# Cool-S-Budget.net
KiCad netlist of a schematic drawn in EAGLE
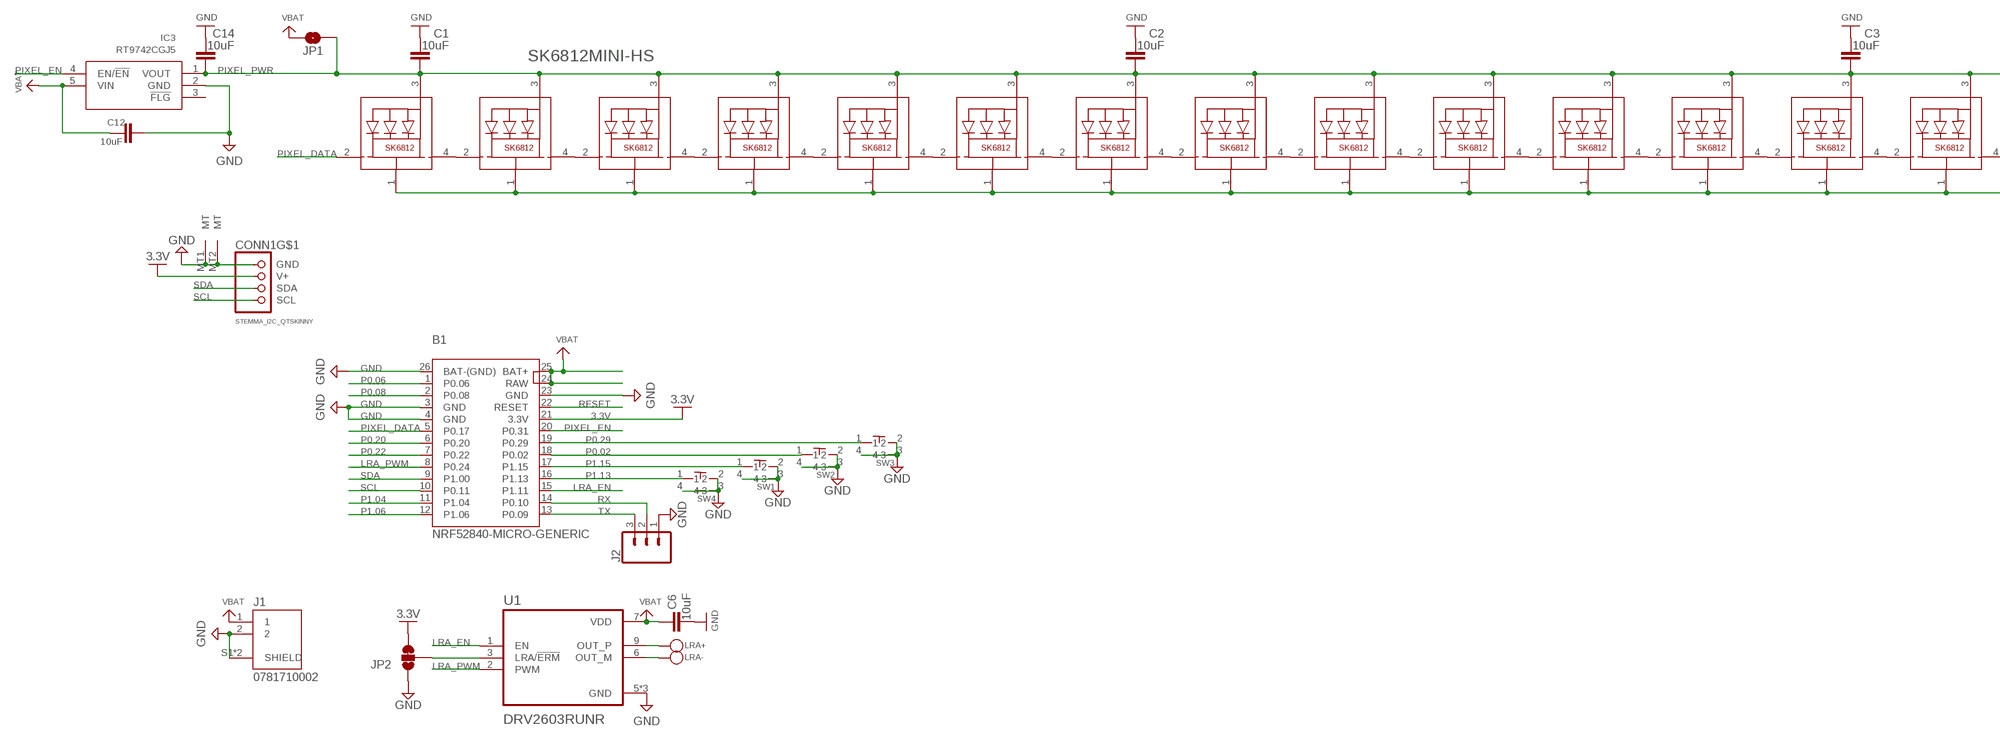
[diagram p0: schematic, sheet 1, part 1 of 2]
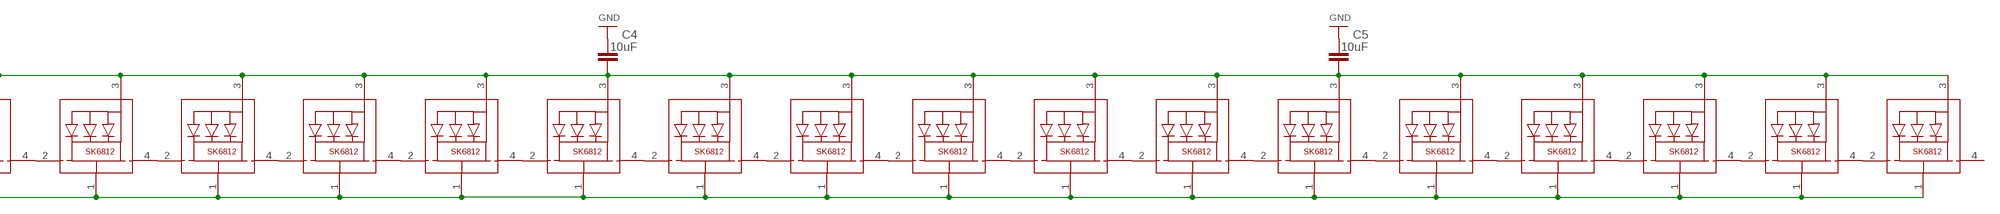
[diagram p1: schematic, sheet 1, part 2 of 2]

(export (version "E")
  (design (tool "Eeschema 10.0.6"))
  (components
    (comp (ref "B1")
      (value "NRF52840-MICRO-GENERIC")
      (footprint "eagle-import:NRF52840-MICRO-GENERIC")
      (libsource (lib "eagle-import") (part "NRF52840-MICRO-GENERIC"))
    )
    (comp (ref "C1")
      (value "10uF")
      (footprint "eagle-import:CAPC1608X85")
      (libsource (lib "eagle-import") (part "CCHIP-0603(1608-METRIC)_"))
    )
    (comp (ref "C2")
      (value "10uF")
      (footprint "eagle-import:CAPC1608X85")
      (libsource (lib "eagle-import") (part "CCHIP-0603(1608-METRIC)_"))
    )
    (comp (ref "C3")
      (value "10uF")
      (footprint "eagle-import:CAPC1608X85")
      (libsource (lib "eagle-import") (part "CCHIP-0603(1608-METRIC)_"))
    )
    (comp (ref "C4")
      (value "10uF")
      (footprint "eagle-import:CAPC1608X85")
      (libsource (lib "eagle-import") (part "CCHIP-0603(1608-METRIC)_"))
    )
    (comp (ref "C5")
      (value "10uF")
      (footprint "eagle-import:CAPC1608X85")
      (libsource (lib "eagle-import") (part "CCHIP-0603(1608-METRIC)_"))
    )
    (comp (ref "C6")
      (value "10uF")
      (footprint "eagle-import:CAPC1608X85")
      (libsource (lib "eagle-import") (part "CCHIP-0603(1608-METRIC)_"))
    )
    (comp (ref "C12")
      (value "10uF")
      (footprint "eagle-import:CAPC1608X85")
      (libsource (lib "eagle-import") (part "CCHIP-0603(1608-METRIC)_"))
    )
    (comp (ref "C14")
      (value "10uF")
      (footprint "eagle-import:CAPC1608X85")
      (libsource (lib "eagle-import") (part "CCHIP-0603(1608-METRIC)_"))
    )
    (comp (ref "CONN1")
      (value "STEMMA_I2C_QTSKINNY")
      (footprint "eagle-import:JST_SH4_SKINNY")
      (libsource (lib "eagle-import") (part "STEMMA_I2C_QTSKINNY"))
    )
    (comp (ref "IC3")
      (value "RT9742CGJ5")
      (footprint "eagle-import:SOT94P280X100-5N")
      (fields
        (field (name "MANUFACTURER_PART_NUMBER") "RT9742GGJ5")
        (field (name "MOUSER_PART_NUMBER") "835-RT9742GGJ5")
      )
      (libsource (lib "eagle-import") (part "RT9742GGJ5"))
    )
    (comp (ref "J1")
      (value "0781710002")
      (footprint "eagle-import:MOLEX_0781710002")
      (fields (field (name "MANUFACTURER") "MOLEX"))
      (libsource (lib "eagle-import") (part "0781710002"))
    )
    (comp (ref "J2")
      (value "455-1750-1-ND")
      (footprint "eagle-import:1X03")
      (libsource (lib "eagle-import") (part "CONN_03"))
    )
    (comp (ref "JP1")
      (value "JUMPER-SMT_2_NO_NO-SILK")
      (footprint "eagle-import:SMT-JUMPER_2_NO_NO-SILK")
      (libsource (lib "eagle-import") (part "JUMPER-SMT_2_NO_NO-SILK"))
    )
    (comp (ref "JP2")
      (value "JUMPER-SMT_3_1-NC_TRACE_NO-SILK")
      (footprint "eagle-import:SMT-JUMPER_3_1-NC_TRACE_NO-SILK")
      (libsource (lib "eagle-import") (part "JUMPER-SMT_3_1-NC_TRACE_NO-SILK"))
    )
    (comp (ref "LRA+")
      (value "TESTPOINT")
      (footprint "eagle-import:TESTPOINT_SMT")
      (libsource (lib "eagle-import") (part "TESTPOINT"))
    )
    (comp (ref "LRA-")
      (value "TESTPOINT")
      (footprint "eagle-import:TESTPOINT_SMT")
      (libsource (lib "eagle-import") (part "TESTPOINT"))
    )
    (comp (ref "SW1")
      (value "TS36CA-0.6250GF031SW-SMD_SHOU_TS36CA-0.6")
      (footprint "eagle-import:SW-SMD_SHOU_TS36CA-0.6")
      (libsource (lib "eagle-import") (part "TS36CA-0.6250GF031SW-SMD_SHOU_TS36CA-0.6"))
    )
    (comp (ref "SW2")
      (value "TS36CA-0.6250GF031SW-SMD_SHOU_TS36CA-0.6")
      (footprint "eagle-import:SW-SMD_SHOU_TS36CA-0.6")
      (libsource (lib "eagle-import") (part "TS36CA-0.6250GF031SW-SMD_SHOU_TS36CA-0.6"))
    )
    (comp (ref "SW3")
      (value "TS36CA-0.6250GF031SW-SMD_SHOU_TS36CA-0.6")
      (footprint "eagle-import:SW-SMD_SHOU_TS36CA-0.6")
      (libsource (lib "eagle-import") (part "TS36CA-0.6250GF031SW-SMD_SHOU_TS36CA-0.6"))
    )
    (comp (ref "SW4")
      (value "TS36CA-0.6250GF031SW-SMD_SHOU_TS36CA-0.6")
      (footprint "eagle-import:SW-SMD_SHOU_TS36CA-0.6")
      (libsource (lib "eagle-import") (part "TS36CA-0.6250GF031SW-SMD_SHOU_TS36CA-0.6"))
    )
    (comp (ref "U1")
      (value "DRV2603RUNR")
      (footprint "eagle-import:QFN50P200X200X80-10N")
      (fields (field (name "MF") "Texas Instruments"))
      (libsource (lib "eagle-import") (part "DRV2603RUNR"))
    )
    (comp (ref "U3")
      (value "SK6812MINI")
      (footprint "eagle-import:LED3535")
      (libsource (lib "eagle-import") (part "SK6812MINI"))
    )
    (comp (ref "U4")
      (value "SK6812MINI")
      (footprint "eagle-import:LED3535")
      (libsource (lib "eagle-import") (part "SK6812MINI"))
    )
    (comp (ref "U5")
      (value "SK6812MINI")
      (footprint "eagle-import:LED3535")
      (libsource (lib "eagle-import") (part "SK6812MINI"))
    )
    (comp (ref "U6")
      (value "SK6812MINI")
      (footprint "eagle-import:LED3535")
      (libsource (lib "eagle-import") (part "SK6812MINI"))
    )
    (comp (ref "U7")
      (value "SK6812MINI")
      (footprint "eagle-import:LED3535")
      (libsource (lib "eagle-import") (part "SK6812MINI"))
    )
    (comp (ref "U8")
      (value "SK6812MINI")
      (footprint "eagle-import:LED3535")
      (libsource (lib "eagle-import") (part "SK6812MINI"))
    )
    (comp (ref "U9")
      (value "SK6812MINI")
      (footprint "eagle-import:LED3535")
      (libsource (lib "eagle-import") (part "SK6812MINI"))
    )
    (comp (ref "U10")
      (value "SK6812MINI")
      (footprint "eagle-import:LED3535")
      (libsource (lib "eagle-import") (part "SK6812MINI"))
    )
    (comp (ref "U11")
      (value "SK6812MINI")
      (footprint "eagle-import:LED3535")
      (libsource (lib "eagle-import") (part "SK6812MINI"))
    )
    (comp (ref "U12")
      (value "SK6812MINI")
      (footprint "eagle-import:LED3535")
      (libsource (lib "eagle-import") (part "SK6812MINI"))
    )
    (comp (ref "U13")
      (value "SK6812MINI")
      (footprint "eagle-import:LED3535")
      (libsource (lib "eagle-import") (part "SK6812MINI"))
    )
    (comp (ref "U14")
      (value "SK6812MINI")
      (footprint "eagle-import:LED3535")
      (libsource (lib "eagle-import") (part "SK6812MINI"))
    )
    (comp (ref "U15")
      (value "SK6812MINI")
      (footprint "eagle-import:LED3535")
      (libsource (lib "eagle-import") (part "SK6812MINI"))
    )
    (comp (ref "U16")
      (value "SK6812MINI")
      (footprint "eagle-import:LED3535")
      (libsource (lib "eagle-import") (part "SK6812MINI"))
    )
    (comp (ref "U17")
      (value "SK6812MINI")
      (footprint "eagle-import:LED3535")
      (libsource (lib "eagle-import") (part "SK6812MINI"))
    )
    (comp (ref "U18")
      (value "SK6812MINI")
      (footprint "eagle-import:LED3535")
      (libsource (lib "eagle-import") (part "SK6812MINI"))
    )
    (comp (ref "U19")
      (value "SK6812MINI")
      (footprint "eagle-import:LED3535")
      (libsource (lib "eagle-import") (part "SK6812MINI"))
    )
    (comp (ref "U20")
      (value "SK6812MINI")
      (footprint "eagle-import:LED3535")
      (libsource (lib "eagle-import") (part "SK6812MINI"))
    )
    (comp (ref "U21")
      (value "SK6812MINI")
      (footprint "eagle-import:LED3535")
      (libsource (lib "eagle-import") (part "SK6812MINI"))
    )
    (comp (ref "U22")
      (value "SK6812MINI")
      (footprint "eagle-import:LED3535")
      (libsource (lib "eagle-import") (part "SK6812MINI"))
    )
    (comp (ref "U23")
      (value "SK6812MINI")
      (footprint "eagle-import:LED3535")
      (libsource (lib "eagle-import") (part "SK6812MINI"))
    )
    (comp (ref "U24")
      (value "SK6812MINI")
      (footprint "eagle-import:LED3535")
      (libsource (lib "eagle-import") (part "SK6812MINI"))
    )
    (comp (ref "U25")
      (value "SK6812MINI")
      (footprint "eagle-import:LED3535")
      (libsource (lib "eagle-import") (part "SK6812MINI"))
    )
    (comp (ref "U26")
      (value "SK6812MINI")
      (footprint "eagle-import:LED3535")
      (libsource (lib "eagle-import") (part "SK6812MINI"))
    )
    (comp (ref "U27")
      (value "SK6812MINI")
      (footprint "eagle-import:LED3535")
      (libsource (lib "eagle-import") (part "SK6812MINI"))
    )
    (comp (ref "U28")
      (value "SK6812MINI")
      (footprint "eagle-import:LED3535")
      (libsource (lib "eagle-import") (part "SK6812MINI"))
    )
    (comp (ref "U29")
      (value "SK6812MINI")
      (footprint "eagle-import:LED3535")
      (libsource (lib "eagle-import") (part "SK6812MINI"))
    )
    (comp (ref "U30")
      (value "SK6812MINI")
      (footprint "eagle-import:LED3535")
      (libsource (lib "eagle-import") (part "SK6812MINI"))
    )
    (comp (ref "U31")
      (value "SK6812MINI")
      (footprint "eagle-import:LED3535")
      (libsource (lib "eagle-import") (part "SK6812MINI"))
    )
    (comp (ref "U32")
      (value "SK6812MINI")
      (footprint "eagle-import:LED3535")
      (libsource (lib "eagle-import") (part "SK6812MINI"))
    )
  )
  (nets
    (net (code "1") (name "/LRA_EN") (class "Default")
      (node (ref "B1") (pin "15") (pinfunction "P1.11_15") (pintype "bidirectional"))
      (node (ref "U1") (pin "1") (pinfunction "EN_1") (pintype "input"))
    )
    (net (code "2") (name "/LRA_PWM") (class "Default")
      (node (ref "B1") (pin "8") (pinfunction "P0.24_8") (pintype "bidirectional"))
      (node (ref "U1") (pin "2") (pinfunction "PWM_2") (pintype "input"))
    )
    (net (code "3") (name "/P0.02") (class "Default")
      (node (ref "B1") (pin "18") (pinfunction "P0.02_18") (pintype "bidirectional"))
      (node (ref "SW2") (pin "1") (pinfunction "1_1") (pintype "bidirectional"))
    )
    (net (code "4") (name "/P0.06") (class "Default")
      (node (ref "B1") (pin "1") (pinfunction "P0.06_1") (pintype "bidirectional"))
    )
    (net (code "5") (name "/P0.08") (class "Default")
      (node (ref "B1") (pin "2") (pinfunction "P0.08_2") (pintype "bidirectional"))
    )
    (net (code "6") (name "/P0.20") (class "Default")
      (node (ref "B1") (pin "6") (pinfunction "P0.20_6") (pintype "bidirectional"))
    )
    (net (code "7") (name "/P0.22") (class "Default")
      (node (ref "B1") (pin "7") (pinfunction "P0.22_7") (pintype "bidirectional"))
    )
    (net (code "8") (name "/P0.29") (class "Default")
      (node (ref "B1") (pin "19") (pinfunction "P0.29_19") (pintype "bidirectional"))
      (node (ref "SW3") (pin "1") (pinfunction "1_1") (pintype "bidirectional"))
    )
    (net (code "9") (name "/P1.04") (class "Default")
      (node (ref "B1") (pin "11") (pinfunction "P1.04_11") (pintype "bidirectional"))
    )
    (net (code "10") (name "/P1.06") (class "Default")
      (node (ref "B1") (pin "12") (pinfunction "P1.06_12") (pintype "bidirectional"))
    )
    (net (code "11") (name "/P1.13") (class "Default")
      (node (ref "B1") (pin "16") (pinfunction "P1.13_16") (pintype "bidirectional"))
      (node (ref "SW4") (pin "1") (pinfunction "1_1") (pintype "bidirectional"))
    )
    (net (code "12") (name "/P1.15") (class "Default")
      (node (ref "B1") (pin "17") (pinfunction "P1.15_17") (pintype "bidirectional"))
      (node (ref "SW1") (pin "1") (pinfunction "1_1") (pintype "bidirectional"))
    )
    (net (code "13") (name "/PIXEL_DATA") (class "Default")
      (node (ref "B1") (pin "5") (pinfunction "P0.17_5") (pintype "bidirectional"))
      (node (ref "U32") (pin "2") (pinfunction "DI_2") (pintype "input"))
    )
    (net (code "14") (name "/PIXEL_EN") (class "Default")
      (node (ref "B1") (pin "20") (pinfunction "P0.31_20") (pintype "bidirectional"))
      (node (ref "IC3") (pin "4") (pinfunction "EN/~{EN}_4") (pintype "bidirectional"))
    )
    (net (code "15") (name "/PIXEL_PWR") (class "Default")
      (node (ref "C1") (pin "2") (pinfunction "2_2") (pintype "passive"))
      (node (ref "C14") (pin "2") (pinfunction "2_2") (pintype "passive"))
      (node (ref "C2") (pin "2") (pinfunction "2_2") (pintype "passive"))
      (node (ref "C3") (pin "2") (pinfunction "2_2") (pintype "passive"))
      (node (ref "C4") (pin "2") (pinfunction "2_2") (pintype "passive"))
      (node (ref "C5") (pin "2") (pinfunction "2_2") (pintype "passive"))
      (node (ref "IC3") (pin "1") (pinfunction "VOUT_1") (pintype "bidirectional"))
      (node (ref "JP1") (pin "1") (pinfunction "1_1") (pintype "passive"))
      (node (ref "U10") (pin "3") (pinfunction "VDD_3") (pintype "power_in"))
      (node (ref "U11") (pin "3") (pinfunction "VDD_3") (pintype "power_in"))
      (node (ref "U12") (pin "3") (pinfunction "VDD_3") (pintype "power_in"))
      (node (ref "U13") (pin "3") (pinfunction "VDD_3") (pintype "power_in"))
      (node (ref "U14") (pin "3") (pinfunction "VDD_3") (pintype "power_in"))
      (node (ref "U15") (pin "3") (pinfunction "VDD_3") (pintype "power_in"))
      (node (ref "U16") (pin "3") (pinfunction "VDD_3") (pintype "power_in"))
      (node (ref "U17") (pin "3") (pinfunction "VDD_3") (pintype "power_in"))
      (node (ref "U18") (pin "3") (pinfunction "VDD_3") (pintype "power_in"))
      (node (ref "U19") (pin "3") (pinfunction "VDD_3") (pintype "power_in"))
      (node (ref "U20") (pin "3") (pinfunction "VDD_3") (pintype "power_in"))
      (node (ref "U21") (pin "3") (pinfunction "VDD_3") (pintype "power_in"))
      (node (ref "U22") (pin "3") (pinfunction "VDD_3") (pintype "power_in"))
      (node (ref "U23") (pin "3") (pinfunction "VDD_3") (pintype "power_in"))
      (node (ref "U24") (pin "3") (pinfunction "VDD_3") (pintype "power_in"))
      (node (ref "U25") (pin "3") (pinfunction "VDD_3") (pintype "power_in"))
      (node (ref "U26") (pin "3") (pinfunction "VDD_3") (pintype "power_in"))
      (node (ref "U27") (pin "3") (pinfunction "VDD_3") (pintype "power_in"))
      (node (ref "U28") (pin "3") (pinfunction "VDD_3") (pintype "power_in"))
      (node (ref "U29") (pin "3") (pinfunction "VDD_3") (pintype "power_in"))
      (node (ref "U3") (pin "3") (pinfunction "VDD_3") (pintype "power_in"))
      (node (ref "U30") (pin "3") (pinfunction "VDD_3") (pintype "power_in"))
      (node (ref "U31") (pin "3") (pinfunction "VDD_3") (pintype "power_in"))
      (node (ref "U32") (pin "3") (pinfunction "VDD_3") (pintype "power_in"))
      (node (ref "U4") (pin "3") (pinfunction "VDD_3") (pintype "power_in"))
      (node (ref "U5") (pin "3") (pinfunction "VDD_3") (pintype "power_in"))
      (node (ref "U6") (pin "3") (pinfunction "VDD_3") (pintype "power_in"))
      (node (ref "U7") (pin "3") (pinfunction "VDD_3") (pintype "power_in"))
      (node (ref "U8") (pin "3") (pinfunction "VDD_3") (pintype "power_in"))
      (node (ref "U9") (pin "3") (pinfunction "VDD_3") (pintype "power_in"))
    )
    (net (code "16") (name "/RESET") (class "Default")
      (node (ref "B1") (pin "22") (pinfunction "RESET_22") (pintype "bidirectional"))
    )
    (net (code "17") (name "/RX") (class "Default")
      (node (ref "B1") (pin "14") (pinfunction "P0.10_14") (pintype "bidirectional"))
      (node (ref "J2") (pin "2") (pinfunction "2_2") (pintype "passive"))
    )
    (net (code "18") (name "/SCL") (class "Default")
      (node (ref "B1") (pin "10") (pinfunction "P0.11_10") (pintype "bidirectional"))
      (node (ref "CONN1") (pin "4") (pinfunction "SCL_4") (pintype "passive"))
    )
    (net (code "19") (name "/SDA") (class "Default")
      (node (ref "B1") (pin "9") (pinfunction "P1.00_9") (pintype "bidirectional"))
      (node (ref "CONN1") (pin "3") (pinfunction "SDA_3") (pintype "passive"))
    )
    (net (code "20") (name "/TX") (class "Default")
      (node (ref "B1") (pin "13") (pinfunction "P0.09_13") (pintype "bidirectional"))
      (node (ref "J2") (pin "3") (pinfunction "3_3") (pintype "passive"))
    )
    (net (code "21") (name "3.3V") (class "Default")
      (node (ref "B1") (pin "21") (pinfunction "3.3V_21") (pintype "power_in"))
      (node (ref "CONN1") (pin "2") (pinfunction "V+_2") (pintype "passive"))
      (node (ref "JP2") (pin "3") (pinfunction "3_3") (pintype "passive"))
    )
    (net (code "22") (name "GND") (class "Default")
      (node (ref "B1") (pin "23") (pinfunction "GND_23") (pintype "power_in"))
      (node (ref "B1") (pin "26") (pinfunction "BAT-(GND)_26") (pintype "bidirectional"))
      (node (ref "B1") (pin "3") (pinfunction "GND_3") (pintype "power_in"))
      (node (ref "B1") (pin "4") (pinfunction "GND_4") (pintype "power_in"))
      (node (ref "C1") (pin "1") (pinfunction "1_1") (pintype "passive"))
      (node (ref "C12") (pin "2") (pinfunction "2_2") (pintype "passive"))
      (node (ref "C14") (pin "1") (pinfunction "1_1") (pintype "passive"))
      (node (ref "C2") (pin "1") (pinfunction "1_1") (pintype "passive"))
      (node (ref "C3") (pin "1") (pinfunction "1_1") (pintype "passive"))
      (node (ref "C4") (pin "1") (pinfunction "1_1") (pintype "passive"))
      (node (ref "C5") (pin "1") (pinfunction "1_1") (pintype "passive"))
      (node (ref "C6") (pin "1") (pinfunction "1_1") (pintype "passive"))
      (node (ref "CONN1") (pin "1") (pinfunction "GND_1") (pintype "passive"))
      (node (ref "CONN1") (pin "MT1") (pinfunction "MT_MT1") (pintype "bidirectional"))
      (node (ref "CONN1") (pin "MT2") (pinfunction "MT_MT2") (pintype "bidirectional"))
      (node (ref "IC3") (pin "2") (pinfunction "GND_2") (pintype "bidirectional"))
      (node (ref "J1") (pin "2") (pinfunction "2_2") (pintype "passive"))
      (node (ref "J1") (pin "S1") (pinfunction "SHIELD_S1") (pintype "passive"))
      (node (ref "J1") (pin "S2") (pinfunction "SHIELD_S2") (pintype "passive"))
      (node (ref "J2") (pin "1") (pinfunction "1_1") (pintype "passive"))
      (node (ref "JP2") (pin "1") (pinfunction "1_1") (pintype "passive"))
      (node (ref "SW1") (pin "2") (pinfunction "2_2") (pintype "bidirectional"))
      (node (ref "SW1") (pin "3") (pinfunction "3_3") (pintype "bidirectional"))
      (node (ref "SW1") (pin "4") (pinfunction "4_4") (pintype "bidirectional"))
      (node (ref "SW2") (pin "2") (pinfunction "2_2") (pintype "bidirectional"))
      (node (ref "SW2") (pin "3") (pinfunction "3_3") (pintype "bidirectional"))
      (node (ref "SW2") (pin "4") (pinfunction "4_4") (pintype "bidirectional"))
      (node (ref "SW3") (pin "2") (pinfunction "2_2") (pintype "bidirectional"))
      (node (ref "SW3") (pin "3") (pinfunction "3_3") (pintype "bidirectional"))
      (node (ref "SW3") (pin "4") (pinfunction "4_4") (pintype "bidirectional"))
      (node (ref "SW4") (pin "2") (pinfunction "2_2") (pintype "bidirectional"))
      (node (ref "SW4") (pin "3") (pinfunction "3_3") (pintype "bidirectional"))
      (node (ref "SW4") (pin "4") (pinfunction "4_4") (pintype "bidirectional"))
      (node (ref "U1") (pin "10") (pinfunction "GND_10") (pintype "power_in"))
      (node (ref "U1") (pin "5") (pinfunction "GND_5") (pintype "power_in"))
      (node (ref "U1") (pin "8") (pinfunction "GND_8") (pintype "power_in"))
      (node (ref "U10") (pin "1") (pinfunction "GND_1") (pintype "power_in"))
      (node (ref "U11") (pin "1") (pinfunction "GND_1") (pintype "power_in"))
      (node (ref "U12") (pin "1") (pinfunction "GND_1") (pintype "power_in"))
      (node (ref "U13") (pin "1") (pinfunction "GND_1") (pintype "power_in"))
      (node (ref "U14") (pin "1") (pinfunction "GND_1") (pintype "power_in"))
      (node (ref "U15") (pin "1") (pinfunction "GND_1") (pintype "power_in"))
      (node (ref "U16") (pin "1") (pinfunction "GND_1") (pintype "power_in"))
      (node (ref "U17") (pin "1") (pinfunction "GND_1") (pintype "power_in"))
      (node (ref "U18") (pin "1") (pinfunction "GND_1") (pintype "power_in"))
      (node (ref "U19") (pin "1") (pinfunction "GND_1") (pintype "power_in"))
      (node (ref "U20") (pin "1") (pinfunction "GND_1") (pintype "power_in"))
      (node (ref "U21") (pin "1") (pinfunction "GND_1") (pintype "power_in"))
      (node (ref "U22") (pin "1") (pinfunction "GND_1") (pintype "power_in"))
      (node (ref "U23") (pin "1") (pinfunction "GND_1") (pintype "power_in"))
      (node (ref "U24") (pin "1") (pinfunction "GND_1") (pintype "power_in"))
      (node (ref "U25") (pin "1") (pinfunction "GND_1") (pintype "power_in"))
      (node (ref "U26") (pin "1") (pinfunction "GND_1") (pintype "power_in"))
      (node (ref "U27") (pin "1") (pinfunction "GND_1") (pintype "power_in"))
      (node (ref "U28") (pin "1") (pinfunction "GND_1") (pintype "power_in"))
      (node (ref "U29") (pin "1") (pinfunction "GND_1") (pintype "power_in"))
      (node (ref "U3") (pin "1") (pinfunction "GND_1") (pintype "power_in"))
      (node (ref "U30") (pin "1") (pinfunction "GND_1") (pintype "power_in"))
      (node (ref "U31") (pin "1") (pinfunction "GND_1") (pintype "power_in"))
      (node (ref "U32") (pin "1") (pinfunction "GND_1") (pintype "power_in"))
      (node (ref "U4") (pin "1") (pinfunction "GND_1") (pintype "power_in"))
      (node (ref "U5") (pin "1") (pinfunction "GND_1") (pintype "power_in"))
      (node (ref "U6") (pin "1") (pinfunction "GND_1") (pintype "power_in"))
      (node (ref "U7") (pin "1") (pinfunction "GND_1") (pintype "power_in"))
      (node (ref "U8") (pin "1") (pinfunction "GND_1") (pintype "power_in"))
      (node (ref "U9") (pin "1") (pinfunction "GND_1") (pintype "power_in"))
    )
    (net (code "23") (name "Net-(U1-LRA{slash}~{ERM})") (class "Default")
      (node (ref "JP2") (pin "2") (pinfunction "2_2") (pintype "passive"))
      (node (ref "U1") (pin "3") (pinfunction "LRA/~{ERM}_3") (pintype "input"))
    )
    (net (code "24") (name "Net-(U1-OUT_M)") (class "Default")
      (node (ref "LRA-") (pin "P$1") (pinfunction "P$1_P$1") (pintype "bidirectional"))
      (node (ref "U1") (pin "6") (pinfunction "OUT_M_6") (pintype "output"))
    )
    (net (code "25") (name "Net-(U1-OUT_P)") (class "Default")
      (node (ref "LRA+") (pin "P$1") (pinfunction "P$1_P$1") (pintype "bidirectional"))
      (node (ref "U1") (pin "9") (pinfunction "OUT_P_9") (pintype "output"))
    )
    (net (code "26") (name "Net-(U3-DI)") (class "Default")
      (node (ref "U3") (pin "2") (pinfunction "DI_2") (pintype "input"))
      (node (ref "U4") (pin "4") (pinfunction "DO_4") (pintype "output"))
    )
    (net (code "27") (name "Net-(U4-DI)") (class "Default")
      (node (ref "U4") (pin "2") (pinfunction "DI_2") (pintype "input"))
      (node (ref "U5") (pin "4") (pinfunction "DO_4") (pintype "output"))
    )
    (net (code "28") (name "Net-(U5-DI)") (class "Default")
      (node (ref "U5") (pin "2") (pinfunction "DI_2") (pintype "input"))
      (node (ref "U6") (pin "4") (pinfunction "DO_4") (pintype "output"))
    )
    (net (code "29") (name "Net-(U6-DI)") (class "Default")
      (node (ref "U6") (pin "2") (pinfunction "DI_2") (pintype "input"))
      (node (ref "U7") (pin "4") (pinfunction "DO_4") (pintype "output"))
    )
    (net (code "30") (name "Net-(U7-DI)") (class "Default")
      (node (ref "U7") (pin "2") (pinfunction "DI_2") (pintype "input"))
      (node (ref "U8") (pin "4") (pinfunction "DO_4") (pintype "output"))
    )
    (net (code "31") (name "Net-(U8-DI)") (class "Default")
      (node (ref "U8") (pin "2") (pinfunction "DI_2") (pintype "input"))
      (node (ref "U9") (pin "4") (pinfunction "DO_4") (pintype "output"))
    )
    (net (code "32") (name "Net-(U10-DI)") (class "Default")
      (node (ref "U10") (pin "2") (pinfunction "DI_2") (pintype "input"))
      (node (ref "U11") (pin "4") (pinfunction "DO_4") (pintype "output"))
    )
    (net (code "33") (name "Net-(U10-DO)") (class "Default")
      (node (ref "U10") (pin "4") (pinfunction "DO_4") (pintype "output"))
      (node (ref "U9") (pin "2") (pinfunction "DI_2") (pintype "input"))
    )
    (net (code "34") (name "Net-(U11-DI)") (class "Default")
      (node (ref "U11") (pin "2") (pinfunction "DI_2") (pintype "input"))
      (node (ref "U12") (pin "4") (pinfunction "DO_4") (pintype "output"))
    )
    (net (code "35") (name "Net-(U12-DI)") (class "Default")
      (node (ref "U12") (pin "2") (pinfunction "DI_2") (pintype "input"))
      (node (ref "U13") (pin "4") (pinfunction "DO_4") (pintype "output"))
    )
    (net (code "36") (name "Net-(U13-DI)") (class "Default")
      (node (ref "U13") (pin "2") (pinfunction "DI_2") (pintype "input"))
      (node (ref "U14") (pin "4") (pinfunction "DO_4") (pintype "output"))
    )
    (net (code "37") (name "Net-(U14-DI)") (class "Default")
      (node (ref "U14") (pin "2") (pinfunction "DI_2") (pintype "input"))
      (node (ref "U15") (pin "4") (pinfunction "DO_4") (pintype "output"))
    )
    (net (code "38") (name "Net-(U15-DI)") (class "Default")
      (node (ref "U15") (pin "2") (pinfunction "DI_2") (pintype "input"))
      (node (ref "U16") (pin "4") (pinfunction "DO_4") (pintype "output"))
    )
    (net (code "39") (name "Net-(U16-DI)") (class "Default")
      (node (ref "U16") (pin "2") (pinfunction "DI_2") (pintype "input"))
      (node (ref "U17") (pin "4") (pinfunction "DO_4") (pintype "output"))
    )
    (net (code "40") (name "Net-(U17-DI)") (class "Default")
      (node (ref "U17") (pin "2") (pinfunction "DI_2") (pintype "input"))
      (node (ref "U18") (pin "4") (pinfunction "DO_4") (pintype "output"))
    )
    (net (code "41") (name "Net-(U18-DI)") (class "Default")
      (node (ref "U18") (pin "2") (pinfunction "DI_2") (pintype "input"))
      (node (ref "U19") (pin "4") (pinfunction "DO_4") (pintype "output"))
    )
    (net (code "42") (name "Net-(U19-DI)") (class "Default")
      (node (ref "U19") (pin "2") (pinfunction "DI_2") (pintype "input"))
      (node (ref "U20") (pin "4") (pinfunction "DO_4") (pintype "output"))
    )
    (net (code "43") (name "Net-(U20-DI)") (class "Default")
      (node (ref "U20") (pin "2") (pinfunction "DI_2") (pintype "input"))
      (node (ref "U21") (pin "4") (pinfunction "DO_4") (pintype "output"))
    )
    (net (code "44") (name "Net-(U21-DI)") (class "Default")
      (node (ref "U21") (pin "2") (pinfunction "DI_2") (pintype "input"))
      (node (ref "U22") (pin "4") (pinfunction "DO_4") (pintype "output"))
    )
    (net (code "45") (name "Net-(U22-DI)") (class "Default")
      (node (ref "U22") (pin "2") (pinfunction "DI_2") (pintype "input"))
      (node (ref "U23") (pin "4") (pinfunction "DO_4") (pintype "output"))
    )
    (net (code "46") (name "Net-(U23-DI)") (class "Default")
      (node (ref "U23") (pin "2") (pinfunction "DI_2") (pintype "input"))
      (node (ref "U24") (pin "4") (pinfunction "DO_4") (pintype "output"))
    )
    (net (code "47") (name "Net-(U24-DI)") (class "Default")
      (node (ref "U24") (pin "2") (pinfunction "DI_2") (pintype "input"))
      (node (ref "U25") (pin "4") (pinfunction "DO_4") (pintype "output"))
    )
    (net (code "48") (name "Net-(U25-DI)") (class "Default")
      (node (ref "U25") (pin "2") (pinfunction "DI_2") (pintype "input"))
      (node (ref "U26") (pin "4") (pinfunction "DO_4") (pintype "output"))
    )
    (net (code "49") (name "Net-(U26-DI)") (class "Default")
      (node (ref "U26") (pin "2") (pinfunction "DI_2") (pintype "input"))
      (node (ref "U27") (pin "4") (pinfunction "DO_4") (pintype "output"))
    )
    (net (code "50") (name "Net-(U27-DI)") (class "Default")
      (node (ref "U27") (pin "2") (pinfunction "DI_2") (pintype "input"))
      (node (ref "U28") (pin "4") (pinfunction "DO_4") (pintype "output"))
    )
    (net (code "51") (name "Net-(U28-DI)") (class "Default")
      (node (ref "U28") (pin "2") (pinfunction "DI_2") (pintype "input"))
      (node (ref "U29") (pin "4") (pinfunction "DO_4") (pintype "output"))
    )
    (net (code "52") (name "Net-(U29-DI)") (class "Default")
      (node (ref "U29") (pin "2") (pinfunction "DI_2") (pintype "input"))
      (node (ref "U30") (pin "4") (pinfunction "DO_4") (pintype "output"))
    )
    (net (code "53") (name "Net-(U30-DI)") (class "Default")
      (node (ref "U30") (pin "2") (pinfunction "DI_2") (pintype "input"))
      (node (ref "U31") (pin "4") (pinfunction "DO_4") (pintype "output"))
    )
    (net (code "54") (name "Net-(U31-DI)") (class "Default")
      (node (ref "U31") (pin "2") (pinfunction "DI_2") (pintype "input"))
      (node (ref "U32") (pin "4") (pinfunction "DO_4") (pintype "output"))
    )
    (net (code "55") (name "VBAT") (class "Default")
      (node (ref "B1") (pin "24") (pinfunction "RAW_24") (pintype "power_in"))
      (node (ref "B1") (pin "25") (pinfunction "BAT+_25") (pintype "bidirectional"))
      (node (ref "C12") (pin "1") (pinfunction "1_1") (pintype "passive"))
      (node (ref "C6") (pin "2") (pinfunction "2_2") (pintype "passive"))
      (node (ref "IC3") (pin "5") (pinfunction "VIN_5") (pintype "bidirectional"))
      (node (ref "J1") (pin "1") (pinfunction "1_1") (pintype "passive"))
      (node (ref "JP1") (pin "2") (pinfunction "2_2") (pintype "passive"))
      (node (ref "U1") (pin "7") (pinfunction "VDD_7") (pintype "power_in"))
    )
    (net (code "56") (name "unconnected-(IC3-~{FLG}-Pad3)") (class "Default")
      (node (ref "IC3") (pin "3") (pinfunction "~{FLG}_3") (pintype "bidirectional"))
    )
    (net (code "57") (name "unconnected-(U3-DO-Pad4)") (class "Default")
      (node (ref "U3") (pin "4") (pinfunction "DO_4") (pintype "output"))
    )
  )
)
